# 4-way-charger.net
KiCad netlist of a schematic drawn in EAGLE
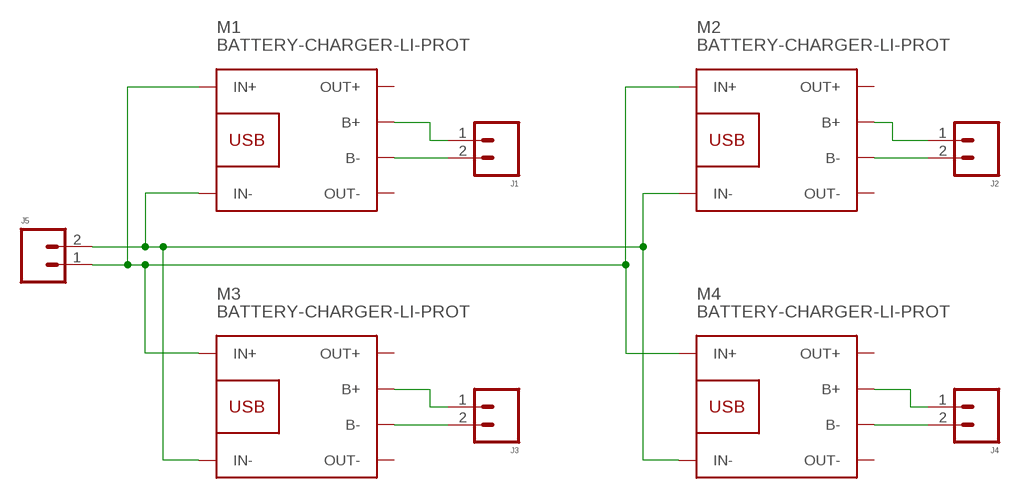
[diagram p0: schematic, sheet 1]

(export (version "E")
  (design (tool "Eeschema 10.0.6"))
  (components
    (comp (ref "J1")
      (value "M02RA_MALE_MILL")
      (footprint "eagle-import:1X02_RA_PTH_MALE_MILL")
      (libsource (lib "eagle-import") (part "M02RA_MALE_MILL"))
    )
    (comp (ref "J2")
      (value "M02RA_MALE_MILL")
      (footprint "eagle-import:1X02_RA_PTH_MALE_MILL")
      (libsource (lib "eagle-import") (part "M02RA_MALE_MILL"))
    )
    (comp (ref "J3")
      (value "M02RA_MALE_MILL")
      (footprint "eagle-import:1X02_RA_PTH_MALE_MILL")
      (libsource (lib "eagle-import") (part "M02RA_MALE_MILL"))
    )
    (comp (ref "J4")
      (value "M02RA_MALE_MILL")
      (footprint "eagle-import:1X02_RA_PTH_MALE_MILL")
      (libsource (lib "eagle-import") (part "M02RA_MALE_MILL"))
    )
    (comp (ref "J5")
      (value "M02RA_MALE_MILL")
      (footprint "eagle-import:1X02_RA_PTH_MALE_MILL")
      (libsource (lib "eagle-import") (part "M02RA_MALE_MILL"))
    )
    (comp (ref "M1")
      (value "BATTERY-CHARGER-LI-PROT")
      (footprint "eagle-import:BATTERY-CHARGER-LI-PROT")
      (libsource (lib "eagle-import") (part "BATTERY-CHARGER-LI-PROT"))
    )
    (comp (ref "M2")
      (value "BATTERY-CHARGER-LI-PROT")
      (footprint "eagle-import:BATTERY-CHARGER-LI-PROT")
      (libsource (lib "eagle-import") (part "BATTERY-CHARGER-LI-PROT"))
    )
    (comp (ref "M3")
      (value "BATTERY-CHARGER-LI-PROT")
      (footprint "eagle-import:BATTERY-CHARGER-LI-PROT")
      (libsource (lib "eagle-import") (part "BATTERY-CHARGER-LI-PROT"))
    )
    (comp (ref "M4")
      (value "BATTERY-CHARGER-LI-PROT")
      (footprint "eagle-import:BATTERY-CHARGER-LI-PROT")
      (libsource (lib "eagle-import") (part "BATTERY-CHARGER-LI-PROT"))
    )
  )
  (nets
    (net (code "1") (name "Net-(J1-Pad1)") (class "Default")
      (node (ref "J1") (pin "1") (pinfunction "1_1") (pintype "passive"))
      (node (ref "M1") (pin "B+") (pinfunction "B+_B+") (pintype "bidirectional"))
    )
    (net (code "2") (name "Net-(J1-Pad2)") (class "Default")
      (node (ref "J1") (pin "2") (pinfunction "2_2") (pintype "passive"))
      (node (ref "M1") (pin "B-") (pinfunction "B-_B-") (pintype "bidirectional"))
    )
    (net (code "3") (name "Net-(J2-Pad1)") (class "Default")
      (node (ref "J2") (pin "1") (pinfunction "1_1") (pintype "passive"))
      (node (ref "M2") (pin "B+") (pinfunction "B+_B+") (pintype "bidirectional"))
    )
    (net (code "4") (name "Net-(J2-Pad2)") (class "Default")
      (node (ref "J2") (pin "2") (pinfunction "2_2") (pintype "passive"))
      (node (ref "M2") (pin "B-") (pinfunction "B-_B-") (pintype "bidirectional"))
    )
    (net (code "5") (name "Net-(J3-Pad1)") (class "Default")
      (node (ref "J3") (pin "1") (pinfunction "1_1") (pintype "passive"))
      (node (ref "M3") (pin "B+") (pinfunction "B+_B+") (pintype "bidirectional"))
    )
    (net (code "6") (name "Net-(J3-Pad2)") (class "Default")
      (node (ref "J3") (pin "2") (pinfunction "2_2") (pintype "passive"))
      (node (ref "M3") (pin "B-") (pinfunction "B-_B-") (pintype "bidirectional"))
    )
    (net (code "7") (name "Net-(J4-Pad1)") (class "Default")
      (node (ref "J4") (pin "1") (pinfunction "1_1") (pintype "passive"))
      (node (ref "M4") (pin "B+") (pinfunction "B+_B+") (pintype "bidirectional"))
    )
    (net (code "8") (name "Net-(J4-Pad2)") (class "Default")
      (node (ref "J4") (pin "2") (pinfunction "2_2") (pintype "passive"))
      (node (ref "M4") (pin "B-") (pinfunction "B-_B-") (pintype "bidirectional"))
    )
    (net (code "9") (name "Net-(J5-Pad1)") (class "Default")
      (node (ref "J5") (pin "1") (pinfunction "1_1") (pintype "passive"))
      (node (ref "M1") (pin "IN+") (pinfunction "IN+_IN+") (pintype "bidirectional"))
      (node (ref "M2") (pin "IN+") (pinfunction "IN+_IN+") (pintype "bidirectional"))
      (node (ref "M3") (pin "IN+") (pinfunction "IN+_IN+") (pintype "bidirectional"))
      (node (ref "M4") (pin "IN+") (pinfunction "IN+_IN+") (pintype "bidirectional"))
    )
    (net (code "10") (name "Net-(J5-Pad2)") (class "Default")
      (node (ref "J5") (pin "2") (pinfunction "2_2") (pintype "passive"))
      (node (ref "M1") (pin "IN-") (pinfunction "IN-_IN-") (pintype "bidirectional"))
      (node (ref "M2") (pin "IN-") (pinfunction "IN-_IN-") (pintype "bidirectional"))
      (node (ref "M3") (pin "IN-") (pinfunction "IN-_IN-") (pintype "bidirectional"))
      (node (ref "M4") (pin "IN-") (pinfunction "IN-_IN-") (pintype "bidirectional"))
    )
    (net (code "11") (name "unconnected-(M1-PadOUT+)") (class "Default")
      (node (ref "M1") (pin "OUT+") (pinfunction "OUT+_OUT+") (pintype "bidirectional"))
    )
    (net (code "12") (name "unconnected-(M1-PadOUT-)") (class "Default")
      (node (ref "M1") (pin "OUT-") (pinfunction "OUT-_OUT-") (pintype "bidirectional"))
    )
    (net (code "13") (name "unconnected-(M2-PadOUT+)") (class "Default")
      (node (ref "M2") (pin "OUT+") (pinfunction "OUT+_OUT+") (pintype "bidirectional"))
    )
    (net (code "14") (name "unconnected-(M2-PadOUT-)") (class "Default")
      (node (ref "M2") (pin "OUT-") (pinfunction "OUT-_OUT-") (pintype "bidirectional"))
    )
    (net (code "15") (name "unconnected-(M3-PadOUT+)") (class "Default")
      (node (ref "M3") (pin "OUT+") (pinfunction "OUT+_OUT+") (pintype "bidirectional"))
    )
    (net (code "16") (name "unconnected-(M3-PadOUT-)") (class "Default")
      (node (ref "M3") (pin "OUT-") (pinfunction "OUT-_OUT-") (pintype "bidirectional"))
    )
    (net (code "17") (name "unconnected-(M4-PadOUT+)") (class "Default")
      (node (ref "M4") (pin "OUT+") (pinfunction "OUT+_OUT+") (pintype "bidirectional"))
    )
    (net (code "18") (name "unconnected-(M4-PadOUT-)") (class "Default")
      (node (ref "M4") (pin "OUT-") (pinfunction "OUT-_OUT-") (pintype "bidirectional"))
    )
  )
)
